# 04_-_MIPI_INTERFACE.net
KiCad netlist of a schematic drawn in Altium Designer
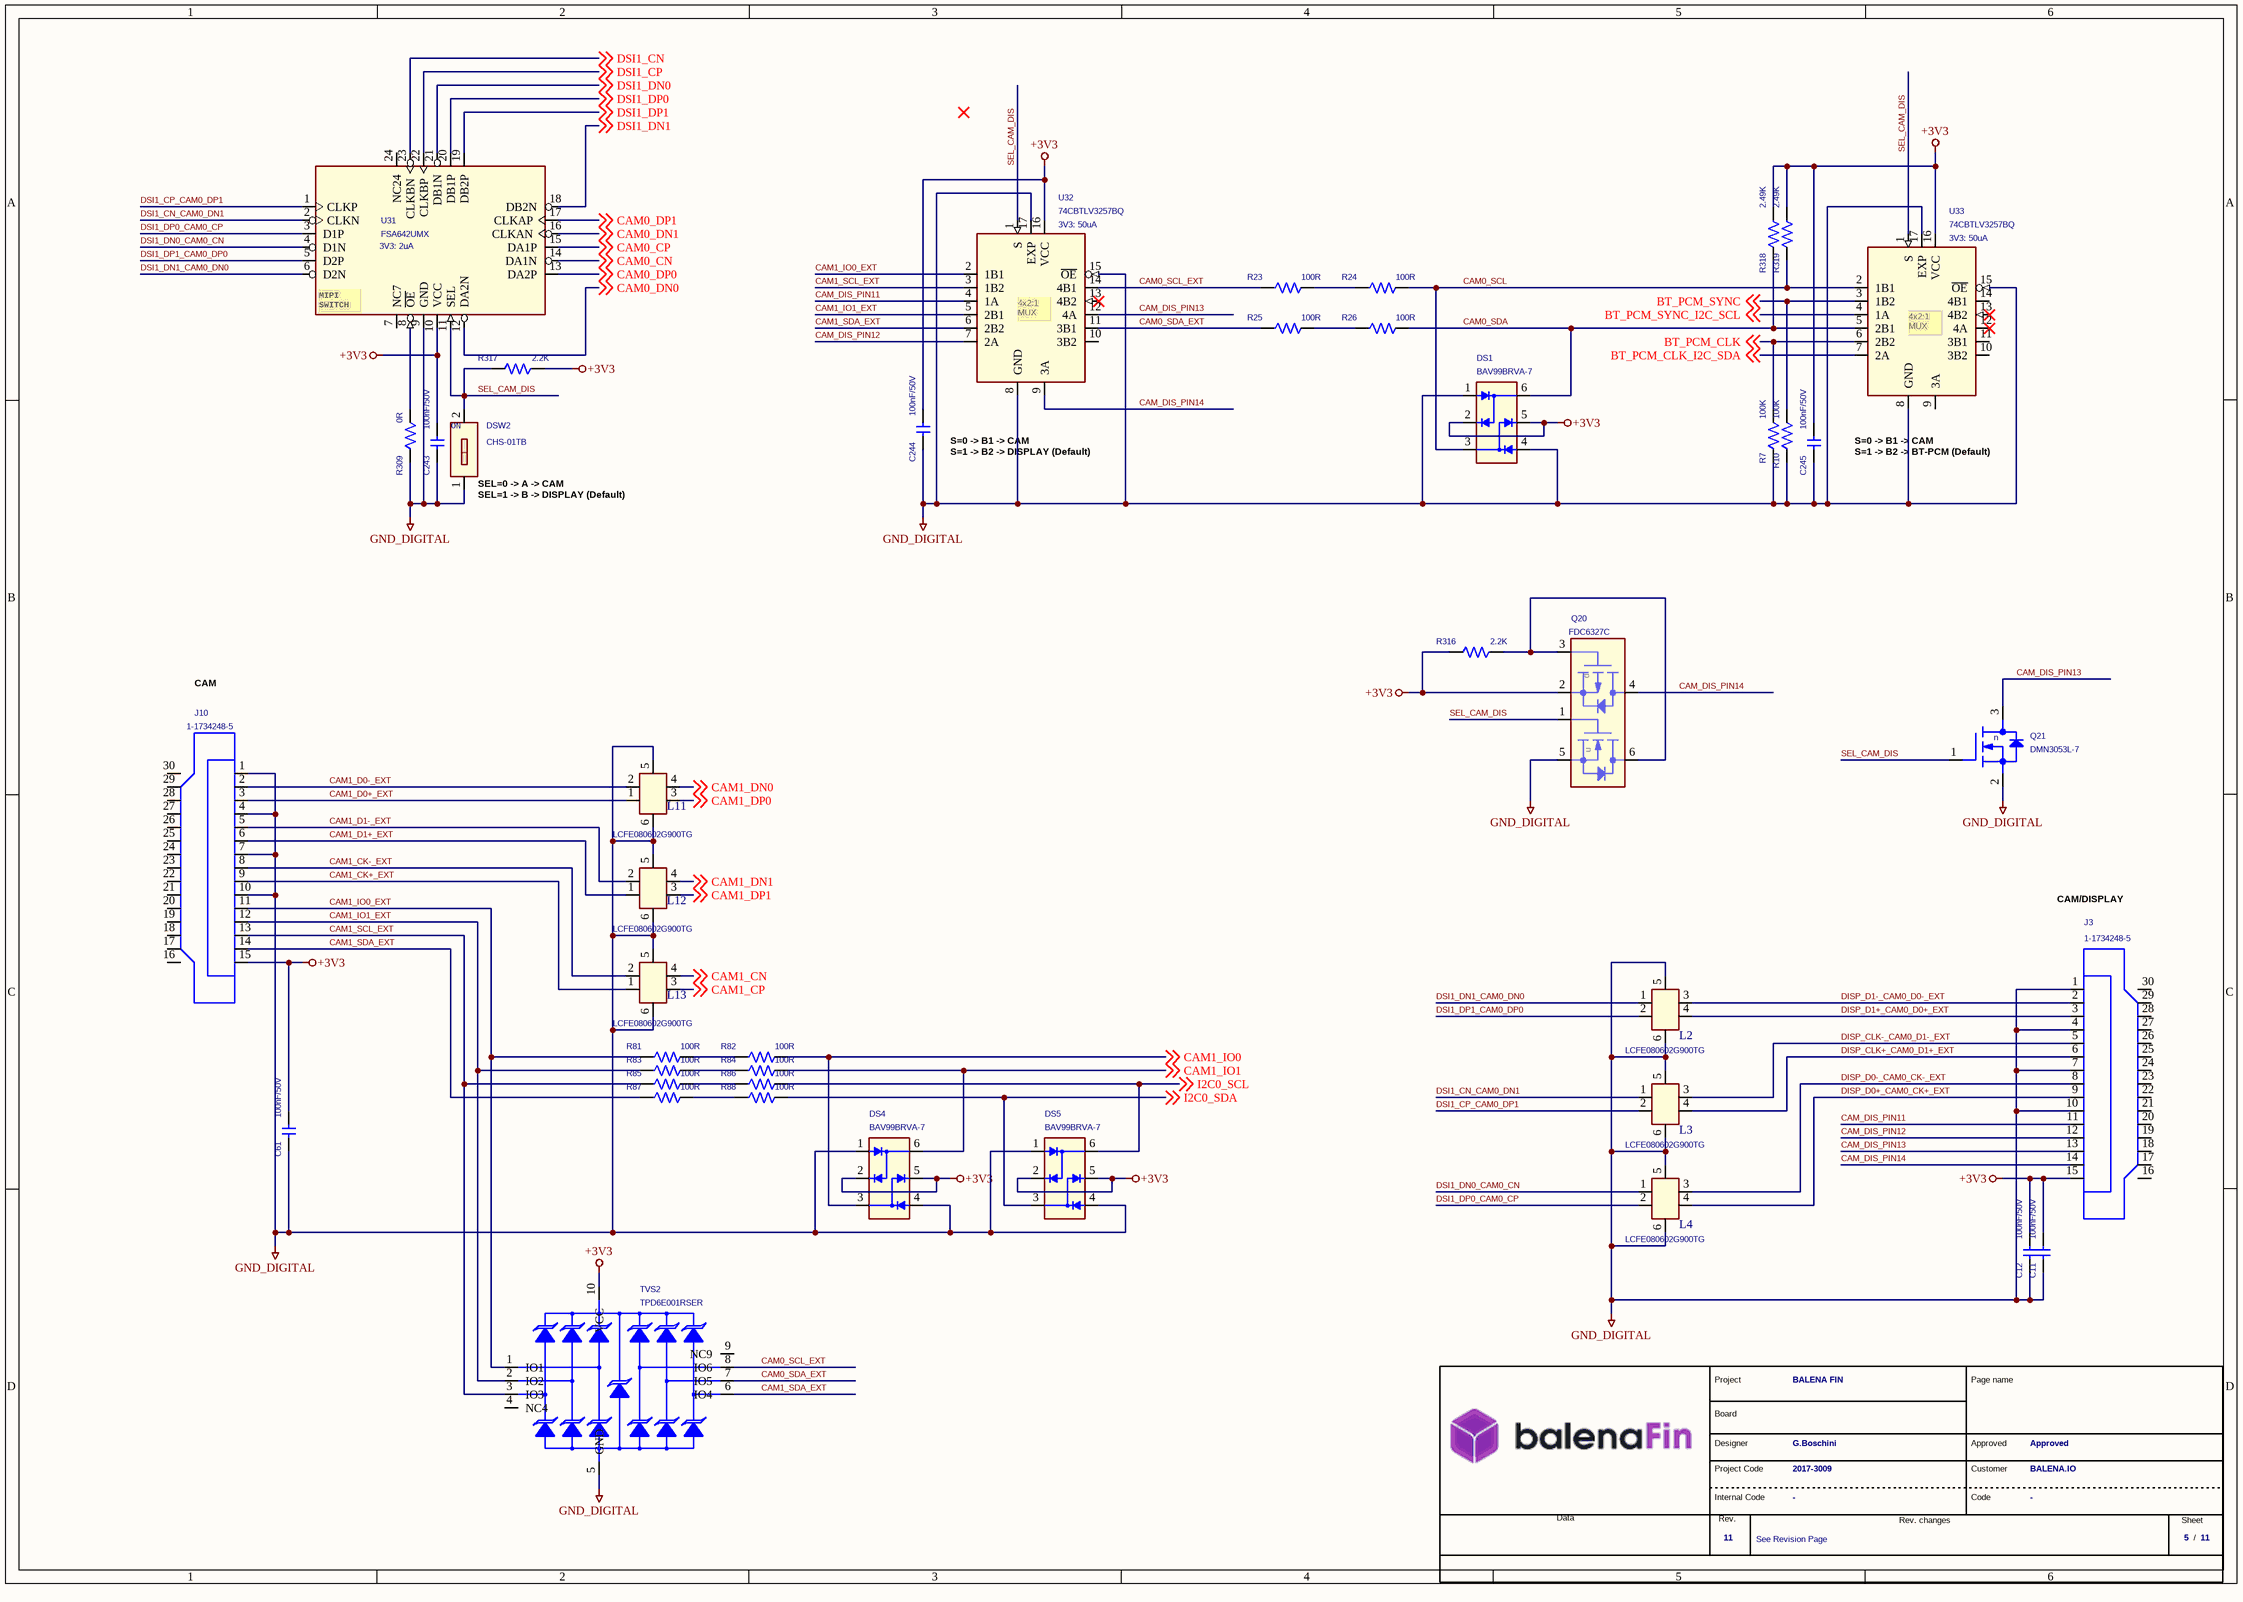
[diagram p0: 04 - MIPI INTERFACE.SchDoc]

(export (version "E")
  (design (tool "Eeschema 10.0.6"))
  (components
    (comp (ref "C11")
      (value "100nF/50V")
      (footprint "CS-C-0402")
      (description "CHIP CAP.CER. 100nF 16V 10% X7R 0402")
      (fields (field (name "MPN") "Generic"))
      (libsource (lib "*") (part "CS-C-0402-100n/16V"))
    )
    (comp (ref "C12")
      (value "100nF/50V")
      (footprint "CS-C-0402")
      (description "CHIP CAP.CER. 100nF 16V 10% X7R 0402")
      (fields (field (name "MPN") "Generic"))
      (libsource (lib "*") (part "CS-C-0402-100n/16V"))
    )
    (comp (ref "C61")
      (value "100nF/50V")
      (footprint "CS-C-0402")
      (description "CHIP CAP.CER. 100nF 16V 10% X7R 0402")
      (fields (field (name "MPN") "Generic"))
      (libsource (lib "*") (part "CS-C-0402-100n/16V"))
    )
    (comp (ref "C243")
      (value "100nF/50V")
      (footprint "CS-C-0402")
      (description "CHIP CAP.CER. 100nF 16V 10% X7R 0402")
      (fields (field (name "MPN") "Generic"))
      (libsource (lib "*") (part "CS-C-0402-100n/16V"))
    )
    (comp (ref "C244")
      (value "100nF/50V")
      (footprint "CS-C-0402")
      (description "CHIP CAP.CER. 100nF 16V 10% X7R 0402")
      (fields (field (name "MPN") "Generic"))
      (libsource (lib "*") (part "CS-C-0402-100n/16V"))
    )
    (comp (ref "C245")
      (value "100nF/50V")
      (footprint "CS-C-0402")
      (description "CHIP CAP.CER. 100nF 16V 10% X7R 0402")
      (fields (field (name "MPN") "Generic"))
      (libsource (lib "*") (part "CS-C-0402-100n/16V"))
    )
    (comp (ref "DS1")
      (value "BAV99BRVA-7")
      (footprint "SOT563")
      (description "Diode Switching 75V 0.215A 6-Pin SOT-563 T/R")
      (libsource (lib "*") (part "DIODO4x - BAV99BRVA-7 -0.2A/75V"))
    )
    (comp (ref "DS4")
      (value "BAV99BRVA-7")
      (footprint "SOT563")
      (description "Diode Switching 75V 0.215A 6-Pin SOT-563 T/R")
      (libsource (lib "*") (part "DIODO4x - BAV99BRVA-7 -0.2A/75V"))
    )
    (comp (ref "DS5")
      (value "BAV99BRVA-7")
      (footprint "SOT563")
      (description "Diode Switching 75V 0.215A 6-Pin SOT-563 T/R")
      (libsource (lib "*") (part "DIODO4x - BAV99BRVA-7 -0.2A/75V"))
    )
    (comp (ref "DSW2")
      (value "CHS-01TB")
      (footprint "DSS-CHS-01TB")
      (description "Dip Switch SPST 1 Position - Surface Mount Slide (Standard) - Actuator 100mA 6VDC")
      (libsource (lib "*") (part "DIP-SW-1x-CHS-01TB-SMD"))
    )
    (comp (ref "J3")
      (value "1-1734248-5")
      (footprint "J-15X2-0100-FDS-ZIF")
      (description "CONN FPC VERT 15POS 1.00MM SMD")
      (libsource (lib "*") (part "FPC-ZIF - J-15X2-0100-FDS-ZIF"))
    )
    (comp (ref "J10")
      (value "1-1734248-5")
      (footprint "J-15X2-0100-FDS-ZIF")
      (description "CONN FPC VERT 15POS 1.00MM SMD")
      (libsource (lib "*") (part "FPC-ZIF - J-15X2-0100-FDS-ZIF"))
    )
    (comp (ref "L2")
      (value "LCFE080602G900TG")
      (footprint "LCFE080602G900TG")
      (description "Common Mode Chokes / Filters 90ohms 25% 100A 2 Lines 0806")
      (libsource (lib "") (part "LCFE080602G900TG_1"))
    )
    (comp (ref "L3")
      (value "LCFE080602G900TG")
      (footprint "LCFE080602G900TG")
      (description "Common Mode Chokes / Filters 90ohms 25% 100A 2 Lines 0806")
      (libsource (lib "") (part "LCFE080602G900TG_1"))
    )
    (comp (ref "L4")
      (value "LCFE080602G900TG")
      (footprint "LCFE080602G900TG")
      (description "Common Mode Chokes / Filters 90ohms 25% 100A 2 Lines 0806")
      (libsource (lib "") (part "LCFE080602G900TG_1"))
    )
    (comp (ref "L11")
      (value "LCFE080602G900TG")
      (footprint "LCFE080602G900TG")
      (description "Common Mode Chokes / Filters 90ohms 25% 100A 2 Lines 0806")
      (libsource (lib "balenaFin_v1_x_x_Library") (part "LCFE080602G900TG"))
    )
    (comp (ref "L12")
      (value "LCFE080602G900TG")
      (footprint "LCFE080602G900TG")
      (description "Common Mode Chokes / Filters 90ohms 25% 100A 2 Lines 0806")
      (libsource (lib "balenaFin_v1_x_x_Library") (part "LCFE080602G900TG"))
    )
    (comp (ref "L13")
      (value "LCFE080602G900TG")
      (footprint "LCFE080602G900TG")
      (description "Common Mode Chokes / Filters 90ohms 25% 100A 2 Lines 0806")
      (libsource (lib "balenaFin_v1_x_x_Library") (part "LCFE080602G900TG"))
    )
    (comp (ref "Q20")
      (value "FDC6327C")
      (footprint "SOT23-6-DBV")
      (description "MOSFET N/P-CH 20V SSOT-6")
      (libsource (lib "*") (part "N-P MOS-FDC6327C-2.7A/1.9A/20V"))
    )
    (comp (ref "Q21")
      (value "DMN3053L-7")
      (footprint "SOT23")
      (description "MOSFET N-CH 30V 4A SOT23")
      (libsource (lib "*") (part "NMOS - DMN3053L-7 - 4A/30V"))
    )
    (comp (ref "R7")
      (value "100K")
      (footprint "RS-0402")
      (description "CHIP RES. 100K 0402 1/16W 1%")
      (fields (field (name "MPN") "Generic"))
      (libsource (lib "*") (part "RS-0402-100k"))
    )
    (comp (ref "R10")
      (value "100K")
      (footprint "RS-0402")
      (description "CHIP RES. 100K 0402 1/16W 1%")
      (fields (field (name "MPN") "Generic"))
      (libsource (lib "*") (part "RS-0402-100k"))
    )
    (comp (ref "R23")
      (value "100R")
      (footprint "RS-0402")
      (description "CHIP RES. 100R 0402 1/16W 1%")
      (fields (field (name "MPN") "Generic"))
      (libsource (lib "*") (part "RS-0402-100r"))
    )
    (comp (ref "R24")
      (value "100R")
      (footprint "RS-0402")
      (description "CHIP RES. 100R 0402 1/16W 1%")
      (fields (field (name "MPN") "Generic"))
      (libsource (lib "*") (part "RS-0402-100r"))
    )
    (comp (ref "R25")
      (value "100R")
      (footprint "RS-0402")
      (description "CHIP RES. 100R 0402 1/16W 1%")
      (fields (field (name "MPN") "Generic"))
      (libsource (lib "*") (part "RS-0402-100r"))
    )
    (comp (ref "R26")
      (value "100R")
      (footprint "RS-0402")
      (description "CHIP RES. 100R 0402 1/16W 1%")
      (fields (field (name "MPN") "Generic"))
      (libsource (lib "*") (part "RS-0402-100r"))
    )
    (comp (ref "R81")
      (value "100R")
      (footprint "RS-0402")
      (description "CHIP RES. 100R 0402 1/16W 1%")
      (fields (field (name "MPN") "Generic"))
      (libsource (lib "*") (part "RS-0402-100r"))
    )
    (comp (ref "R82")
      (value "100R")
      (footprint "RS-0402")
      (description "CHIP RES. 100R 0402 1/16W 1%")
      (fields (field (name "MPN") "Generic"))
      (libsource (lib "*") (part "RS-0402-100r"))
    )
    (comp (ref "R83")
      (value "100R")
      (footprint "RS-0402")
      (description "CHIP RES. 100R 0402 1/16W 1%")
      (fields (field (name "MPN") "Generic"))
      (libsource (lib "*") (part "RS-0402-100r"))
    )
    (comp (ref "R84")
      (value "100R")
      (footprint "RS-0402")
      (description "CHIP RES. 100R 0402 1/16W 1%")
      (fields (field (name "MPN") "Generic"))
      (libsource (lib "*") (part "RS-0402-100r"))
    )
    (comp (ref "R85")
      (value "100R")
      (footprint "RS-0402")
      (description "CHIP RES. 100R 0402 1/16W 1%")
      (fields (field (name "MPN") "Generic"))
      (libsource (lib "*") (part "RS-0402-100r"))
    )
    (comp (ref "R86")
      (value "100R")
      (footprint "RS-0402")
      (description "CHIP RES. 100R 0402 1/16W 1%")
      (fields (field (name "MPN") "Generic"))
      (libsource (lib "*") (part "RS-0402-100r"))
    )
    (comp (ref "R87")
      (value "100R")
      (footprint "RS-0402")
      (description "CHIP RES. 100R 0402 1/16W 1%")
      (fields (field (name "MPN") "Generic"))
      (libsource (lib "*") (part "RS-0402-100r"))
    )
    (comp (ref "R88")
      (value "100R")
      (footprint "RS-0402")
      (description "CHIP RES. 100R 0402 1/16W 1%")
      (fields (field (name "MPN") "Generic"))
      (libsource (lib "*") (part "RS-0402-100r"))
    )
    (comp (ref "R309")
      (value "0R")
      (footprint "RS-0402")
      (description "CHIP RES. 0R 0402 1/16W 1%")
      (fields (field (name "MPN") "Generic"))
      (libsource (lib "*") (part "RS-0402-0r"))
    )
    (comp (ref "R316")
      (value "2.2K")
      (footprint "RS-0402")
      (description "CHIP RES. 2K2 0402 1/16W 1%")
      (fields (field (name "MPN") "Generic"))
      (libsource (lib "*") (part "RS-0402-2.2k"))
    )
    (comp (ref "R317")
      (value "2.2K")
      (footprint "RS-0402")
      (description "CHIP RES. 2K2 0402 1/16W 1%")
      (fields (field (name "MPN") "Generic"))
      (libsource (lib "*") (part "RS-0402-2.2k"))
    )
    (comp (ref "R318")
      (value "2.49K")
      (footprint "RS-0402")
      (description "CHIP RES. 2K49 0402 1/16W 1% 100PPM/°C")
      (fields (field (name "MPN") "Generic"))
      (libsource (lib "*") (part "RS-0402-2.49k"))
    )
    (comp (ref "R319")
      (value "2.49K")
      (footprint "RS-0402")
      (description "CHIP RES. 2K49 0402 1/16W 1% 100PPM/°C")
      (fields (field (name "MPN") "Generic"))
      (libsource (lib "*") (part "RS-0402-2.49k"))
    )
    (comp (ref "TVS2")
      (value "TPD6E001RSER")
      (footprint "UFQFN10")
      (description "TVS DIODE 5VWM")
      (libsource (lib "*") (part "TVS-UNI6x - TPD6E001RSER"))
    )
    (comp (ref "U31")
      (value "FSA642UMX")
      (footprint "UFQFN24-0250X0340")
      (description "IC SWITCH 3PDT 24UMLP")
      (fields (field (name "POWER REQUIREMENTS") "3V3: 2uA"))
      (libsource (lib "*") (part "MIPI-SWITCH - FSA642UMX"))
    )
    (comp (ref "U32")
      (value "74CBTLV3257BQ")
      (footprint "VFQFN16-EXP-0250X0300")
      (description "IC MUX/DEMUX 4 X 1:2 16DHVQFN")
      (fields (field (name "POWER REQUIREMENTS") "3V3: 50uA"))
      (libsource (lib "*") (part "MUX-AN-4x2-1 - 74CBTLV3257BQ"))
    )
    (comp (ref "U33")
      (value "74CBTLV3257BQ")
      (footprint "VFQFN16-EXP-0250X0300")
      (description "IC MUX/DEMUX 4 X 1:2 16DHVQFN")
      (fields (field (name "POWER REQUIREMENTS") "3V3: 50uA"))
      (libsource (lib "*") (part "MUX-AN-4x2-1 - 74CBTLV3257BQ"))
    )
  )
  (nets
    (net (code "1") (name "+3V3") (class "Default")
      (node (ref "C11") (pin "1") (pinfunction "1_1") (pintype "passive"))
      (node (ref "C12") (pin "1") (pinfunction "1_1") (pintype "passive"))
      (node (ref "C243") (pin "1") (pinfunction "1_1") (pintype "passive"))
      (node (ref "C244") (pin "1") (pinfunction "1_1") (pintype "passive"))
      (node (ref "C245") (pin "1") (pinfunction "1_1") (pintype "passive"))
      (node (ref "C61") (pin "1") (pinfunction "1_1") (pintype "passive"))
      (node (ref "DS1") (pin "2") (pinfunction "C1_2") (pintype "passive"))
      (node (ref "DS1") (pin "5") (pinfunction "C2_5") (pintype "passive"))
      (node (ref "DS4") (pin "2") (pinfunction "C1_2") (pintype "passive"))
      (node (ref "DS4") (pin "5") (pinfunction "C2_5") (pintype "passive"))
      (node (ref "DS5") (pin "2") (pinfunction "C1_2") (pintype "passive"))
      (node (ref "DS5") (pin "5") (pinfunction "C2_5") (pintype "passive"))
      (node (ref "J10") (pin "15") (pinfunction "15_15") (pintype "passive"))
      (node (ref "J3") (pin "15") (pinfunction "15_15") (pintype "passive"))
      (node (ref "Q20") (pin "2") (pinfunction "S1_2") (pintype "passive"))
      (node (ref "R316") (pin "2") (pinfunction "2_2") (pintype "passive"))
      (node (ref "R317") (pin "1") (pinfunction "1_1") (pintype "passive"))
      (node (ref "R318") (pin "1") (pinfunction "1_1") (pintype "passive"))
      (node (ref "R319") (pin "1") (pinfunction "1_1") (pintype "passive"))
      (node (ref "TVS2") (pin "10") (pinfunction "VCC_10") (pintype "passive"))
      (node (ref "U31") (pin "10") (pinfunction "VCC_10") (pintype "power_in"))
      (node (ref "U32") (pin "16") (pinfunction "VCC_16") (pintype "power_in"))
      (node (ref "U33") (pin "16") (pinfunction "VCC_16") (pintype "power_in"))
    )
    (net (code "2") (name "/CAM0_SCL") (class "Default")
      (node (ref "DS1") (pin "3") (pinfunction "AC2_3") (pintype "passive"))
      (node (ref "R24") (pin "2") (pinfunction "2_2") (pintype "passive"))
      (node (ref "R319") (pin "2") (pinfunction "2_2") (pintype "passive"))
      (node (ref "U33") (pin "2") (pinfunction "1B1_2") (pintype "bidirectional"))
    )
    (net (code "3") (name "/CAM0_SCL_EXT") (class "Default")
      (node (ref "R23") (pin "1") (pinfunction "1_1") (pintype "passive"))
      (node (ref "TVS2") (pin "8") (pinfunction "IO6_8") (pintype "passive"))
      (node (ref "U32") (pin "14") (pinfunction "4B1_14") (pintype "bidirectional"))
    )
    (net (code "4") (name "/CAM0_SDA") (class "Default")
      (node (ref "DS1") (pin "6") (pinfunction "AC1_6") (pintype "passive"))
      (node (ref "R26") (pin "2") (pinfunction "2_2") (pintype "passive"))
      (node (ref "R318") (pin "2") (pinfunction "2_2") (pintype "passive"))
      (node (ref "U33") (pin "5") (pinfunction "2B1_5") (pintype "bidirectional"))
    )
    (net (code "5") (name "/CAM0_SDA_EXT") (class "Default")
      (node (ref "R25") (pin "1") (pinfunction "1_1") (pintype "passive"))
      (node (ref "TVS2") (pin "7") (pinfunction "IO5_7") (pintype "passive"))
      (node (ref "U32") (pin "11") (pinfunction "3B1_11") (pintype "bidirectional"))
    )
    (net (code "6") (name "/CAM1_CK+_EXT") (class "Default")
      (node (ref "J10") (pin "9") (pinfunction "9_9") (pintype "passive"))
      (node (ref "L13") (pin "1") (pinfunction "1_1") (pintype "passive"))
    )
    (net (code "7") (name "/CAM1_CK-_EXT") (class "Default")
      (node (ref "J10") (pin "8") (pinfunction "8_8") (pintype "passive"))
      (node (ref "L13") (pin "2") (pinfunction "2_2") (pintype "passive"))
    )
    (net (code "8") (name "/CAM1_D0+_EXT") (class "Default")
      (node (ref "J10") (pin "3") (pinfunction "3_3") (pintype "passive"))
      (node (ref "L11") (pin "1") (pinfunction "1_1") (pintype "passive"))
    )
    (net (code "9") (name "/CAM1_D0-_EXT") (class "Default")
      (node (ref "J10") (pin "2") (pinfunction "2_2") (pintype "passive"))
      (node (ref "L11") (pin "2") (pinfunction "2_2") (pintype "passive"))
    )
    (net (code "10") (name "/CAM1_D1+_EXT") (class "Default")
      (node (ref "J10") (pin "6") (pinfunction "6_6") (pintype "passive"))
      (node (ref "L12") (pin "1") (pinfunction "1_1") (pintype "passive"))
    )
    (net (code "11") (name "/CAM1_D1-_EXT") (class "Default")
      (node (ref "J10") (pin "5") (pinfunction "5_5") (pintype "passive"))
      (node (ref "L12") (pin "2") (pinfunction "2_2") (pintype "passive"))
    )
    (net (code "12") (name "/CAM1_IO0_EXT") (class "Default")
      (node (ref "J10") (pin "11") (pinfunction "11_11") (pintype "passive"))
      (node (ref "R81") (pin "1") (pinfunction "1_1") (pintype "passive"))
      (node (ref "TVS2") (pin "1") (pinfunction "IO1_1") (pintype "passive"))
      (node (ref "U32") (pin "2") (pinfunction "1B1_2") (pintype "bidirectional"))
    )
    (net (code "13") (name "/CAM1_IO1_EXT") (class "Default")
      (node (ref "J10") (pin "12") (pinfunction "12_12") (pintype "passive"))
      (node (ref "R83") (pin "1") (pinfunction "1_1") (pintype "passive"))
      (node (ref "TVS2") (pin "2") (pinfunction "IO2_2") (pintype "passive"))
      (node (ref "U32") (pin "5") (pinfunction "2B1_5") (pintype "bidirectional"))
    )
    (net (code "14") (name "/CAM1_SCL_EXT") (class "Default")
      (node (ref "J10") (pin "13") (pinfunction "13_13") (pintype "passive"))
      (node (ref "R85") (pin "1") (pinfunction "1_1") (pintype "passive"))
      (node (ref "TVS2") (pin "3") (pinfunction "IO3_3") (pintype "passive"))
      (node (ref "U32") (pin "3") (pinfunction "1B2_3") (pintype "bidirectional"))
    )
    (net (code "15") (name "/CAM1_SDA_EXT") (class "Default")
      (node (ref "J10") (pin "14") (pinfunction "14_14") (pintype "passive"))
      (node (ref "R87") (pin "1") (pinfunction "1_1") (pintype "passive"))
      (node (ref "TVS2") (pin "6") (pinfunction "IO4_6") (pintype "passive"))
      (node (ref "U32") (pin "6") (pinfunction "2B2_6") (pintype "bidirectional"))
    )
    (net (code "16") (name "/CAM_DIS_PIN11") (class "Default")
      (node (ref "J3") (pin "11") (pinfunction "11_11") (pintype "passive"))
      (node (ref "U32") (pin "4") (pinfunction "1A_4") (pintype "bidirectional"))
    )
    (net (code "17") (name "/CAM_DIS_PIN12") (class "Default")
      (node (ref "J3") (pin "12") (pinfunction "12_12") (pintype "passive"))
      (node (ref "U32") (pin "7") (pinfunction "2A_7") (pintype "bidirectional"))
    )
    (net (code "18") (name "/CAM_DIS_PIN13") (class "Default")
      (node (ref "J3") (pin "13") (pinfunction "13_13") (pintype "passive"))
      (node (ref "Q21") (pin "3") (pinfunction "D_3") (pintype "passive"))
      (node (ref "U32") (pin "12") (pinfunction "4A_12") (pintype "bidirectional"))
    )
    (net (code "19") (name "/CAM_DIS_PIN14") (class "Default")
      (node (ref "J3") (pin "14") (pinfunction "14_14") (pintype "passive"))
      (node (ref "Q20") (pin "4") (pinfunction "D1_4") (pintype "passive"))
      (node (ref "U32") (pin "9") (pinfunction "3A_9") (pintype "bidirectional"))
    )
    (net (code "20") (name "/DISP_CLK+_CAM0_D1+_EXT") (class "Default")
      (node (ref "J3") (pin "6") (pinfunction "6_6") (pintype "passive"))
      (node (ref "L3") (pin "4") (pinfunction "4_4") (pintype "passive"))
    )
    (net (code "21") (name "/DISP_CLK-_CAM0_D1-_EXT") (class "Default")
      (node (ref "J3") (pin "5") (pinfunction "5_5") (pintype "passive"))
      (node (ref "L3") (pin "3") (pinfunction "3_3") (pintype "passive"))
    )
    (net (code "22") (name "/DISP_D0+_CAM0_CK+_EXT") (class "Default")
      (node (ref "J3") (pin "9") (pinfunction "9_9") (pintype "passive"))
      (node (ref "L4") (pin "4") (pinfunction "4_4") (pintype "passive"))
    )
    (net (code "23") (name "/DISP_D0-_CAM0_CK-_EXT") (class "Default")
      (node (ref "J3") (pin "8") (pinfunction "8_8") (pintype "passive"))
      (node (ref "L4") (pin "3") (pinfunction "3_3") (pintype "passive"))
    )
    (net (code "24") (name "/DISP_D1+_CAM0_D0+_EXT") (class "Default")
      (node (ref "J3") (pin "3") (pinfunction "3_3") (pintype "passive"))
      (node (ref "L2") (pin "4") (pinfunction "4_4") (pintype "passive"))
    )
    (net (code "25") (name "/DISP_D1-_CAM0_D0-_EXT") (class "Default")
      (node (ref "J3") (pin "2") (pinfunction "2_2") (pintype "passive"))
      (node (ref "L2") (pin "3") (pinfunction "3_3") (pintype "passive"))
    )
    (net (code "26") (name "/DSI1_CN_CAM0_DN1") (class "Default")
      (node (ref "L3") (pin "1") (pinfunction "1_1") (pintype "passive"))
      (node (ref "U31") (pin "2") (pinfunction "CLKN_2") (pintype "bidirectional"))
    )
    (net (code "27") (name "/DSI1_CP_CAM0_DP1") (class "Default")
      (node (ref "L3") (pin "2") (pinfunction "2_2") (pintype "passive"))
      (node (ref "U31") (pin "1") (pinfunction "CLKP_1") (pintype "bidirectional"))
    )
    (net (code "28") (name "/DSI1_DN0_CAM0_CN") (class "Default")
      (node (ref "L4") (pin "1") (pinfunction "1_1") (pintype "passive"))
      (node (ref "U31") (pin "4") (pinfunction "D1N_4") (pintype "bidirectional"))
    )
    (net (code "29") (name "/DSI1_DN1_CAM0_DN0") (class "Default")
      (node (ref "L2") (pin "1") (pinfunction "1_1") (pintype "passive"))
      (node (ref "U31") (pin "6") (pinfunction "D2N_6") (pintype "bidirectional"))
    )
    (net (code "30") (name "/DSI1_DP0_CAM0_CP") (class "Default")
      (node (ref "L4") (pin "2") (pinfunction "2_2") (pintype "passive"))
      (node (ref "U31") (pin "3") (pinfunction "D1P_3") (pintype "bidirectional"))
    )
    (net (code "31") (name "/DSI1_DP1_CAM0_DP0") (class "Default")
      (node (ref "L2") (pin "2") (pinfunction "2_2") (pintype "passive"))
      (node (ref "U31") (pin "5") (pinfunction "D2P_5") (pintype "bidirectional"))
    )
    (net (code "32") (name "/SEL_CAM_DIS") (class "Default")
      (node (ref "DSW2") (pin "2") (pinfunction "2_2") (pintype "passive"))
      (node (ref "Q20") (pin "1") (pinfunction "G2_1") (pintype "passive"))
      (node (ref "Q21") (pin "1") (pinfunction "G_1") (pintype "passive"))
      (node (ref "R317") (pin "2") (pinfunction "2_2") (pintype "passive"))
      (node (ref "U31") (pin "11") (pinfunction "SEL_11") (pintype "input"))
      (node (ref "U32") (pin "1") (pinfunction "S_1") (pintype "input"))
      (node (ref "U33") (pin "1") (pinfunction "S_1") (pintype "input"))
    )
    (net (code "33") (name "BT_PCM_CLK") (class "Default")
      (node (ref "R7") (pin "2") (pinfunction "2_2") (pintype "passive"))
      (node (ref "U33") (pin "6") (pinfunction "2B2_6") (pintype "bidirectional"))
    )
    (net (code "34") (name "BT_PCM_CLK_I2C_SDA") (class "Default")
      (node (ref "U33") (pin "7") (pinfunction "2A_7") (pintype "bidirectional"))
    )
    (net (code "35") (name "BT_PCM_SYNC") (class "Default")
      (node (ref "R10") (pin "2") (pinfunction "2_2") (pintype "passive"))
      (node (ref "U33") (pin "3") (pinfunction "1B2_3") (pintype "bidirectional"))
    )
    (net (code "36") (name "BT_PCM_SYNC_I2C_SCL") (class "Default")
      (node (ref "U33") (pin "4") (pinfunction "1A_4") (pintype "bidirectional"))
    )
    (net (code "37") (name "CAM0_CN") (class "Default")
      (node (ref "U31") (pin "14") (pinfunction "DA1N_14") (pintype "bidirectional"))
    )
    (net (code "38") (name "CAM0_CP") (class "Default")
      (node (ref "U31") (pin "15") (pinfunction "DA1P_15") (pintype "bidirectional"))
    )
    (net (code "39") (name "CAM0_DN0") (class "Default")
      (node (ref "U31") (pin "12") (pinfunction "DA2N_12") (pintype "bidirectional"))
    )
    (net (code "40") (name "CAM0_DN1") (class "Default")
      (node (ref "U31") (pin "16") (pinfunction "CLKAN_16") (pintype "bidirectional"))
    )
    (net (code "41") (name "CAM0_DP0") (class "Default")
      (node (ref "U31") (pin "13") (pinfunction "DA2P_13") (pintype "bidirectional"))
    )
    (net (code "42") (name "CAM0_DP1") (class "Default")
      (node (ref "U31") (pin "17") (pinfunction "CLKAP_17") (pintype "bidirectional"))
    )
    (net (code "43") (name "CAM1_CN") (class "Default")
      (node (ref "L13") (pin "4") (pinfunction "4_4") (pintype "passive"))
    )
    (net (code "44") (name "CAM1_CP") (class "Default")
      (node (ref "L13") (pin "3") (pinfunction "3_3") (pintype "passive"))
    )
    (net (code "45") (name "CAM1_DN0") (class "Default")
      (node (ref "L11") (pin "4") (pinfunction "4_4") (pintype "passive"))
    )
    (net (code "46") (name "CAM1_DN1") (class "Default")
      (node (ref "L12") (pin "4") (pinfunction "4_4") (pintype "passive"))
    )
    (net (code "47") (name "CAM1_DP0") (class "Default")
      (node (ref "L11") (pin "3") (pinfunction "3_3") (pintype "passive"))
    )
    (net (code "48") (name "CAM1_DP1") (class "Default")
      (node (ref "L12") (pin "3") (pinfunction "3_3") (pintype "passive"))
    )
    (net (code "49") (name "CAM1_IO0") (class "Default")
      (node (ref "DS4") (pin "3") (pinfunction "AC2_3") (pintype "passive"))
      (node (ref "R82") (pin "2") (pinfunction "2_2") (pintype "passive"))
    )
    (net (code "50") (name "CAM1_IO1") (class "Default")
      (node (ref "DS4") (pin "6") (pinfunction "AC1_6") (pintype "passive"))
      (node (ref "R84") (pin "2") (pinfunction "2_2") (pintype "passive"))
    )
    (net (code "51") (name "DSI1_CN") (class "Default")
      (node (ref "U31") (pin "23") (pinfunction "CLKBN_23") (pintype "bidirectional"))
    )
    (net (code "52") (name "DSI1_CP") (class "Default")
      (node (ref "U31") (pin "22") (pinfunction "CLKBP_22") (pintype "bidirectional"))
    )
    (net (code "53") (name "DSI1_DN0") (class "Default")
      (node (ref "U31") (pin "21") (pinfunction "DB1N_21") (pintype "bidirectional"))
    )
    (net (code "54") (name "DSI1_DN1") (class "Default")
      (node (ref "U31") (pin "18") (pinfunction "DB2N_18") (pintype "bidirectional"))
    )
    (net (code "55") (name "DSI1_DP0") (class "Default")
      (node (ref "U31") (pin "20") (pinfunction "DB1P_20") (pintype "bidirectional"))
    )
    (net (code "56") (name "DSI1_DP1") (class "Default")
      (node (ref "U31") (pin "19") (pinfunction "DB2P_19") (pintype "bidirectional"))
    )
    (net (code "57") (name "GND_DIGITAL") (class "Default")
      (node (ref "C11") (pin "2") (pinfunction "2_2") (pintype "passive"))
      (node (ref "C12") (pin "2") (pinfunction "2_2") (pintype "passive"))
      (node (ref "C243") (pin "2") (pinfunction "2_2") (pintype "passive"))
      (node (ref "C244") (pin "2") (pinfunction "2_2") (pintype "passive"))
      (node (ref "C245") (pin "2") (pinfunction "2_2") (pintype "passive"))
      (node (ref "C61") (pin "2") (pinfunction "2_2") (pintype "passive"))
      (node (ref "DS1") (pin "1") (pinfunction "A1_1") (pintype "passive"))
      (node (ref "DS1") (pin "4") (pinfunction "A2_4") (pintype "passive"))
      (node (ref "DS4") (pin "1") (pinfunction "A1_1") (pintype "passive"))
      (node (ref "DS4") (pin "4") (pinfunction "A2_4") (pintype "passive"))
      (node (ref "DS5") (pin "1") (pinfunction "A1_1") (pintype "passive"))
      (node (ref "DS5") (pin "4") (pinfunction "A2_4") (pintype "passive"))
      (node (ref "DSW2") (pin "1") (pinfunction "1_1") (pintype "passive"))
      (node (ref "J10") (pin "1") (pinfunction "1_1") (pintype "passive"))
      (node (ref "J10") (pin "10") (pinfunction "10_10") (pintype "passive"))
      (node (ref "J10") (pin "4") (pinfunction "4_4") (pintype "passive"))
      (node (ref "J10") (pin "7") (pinfunction "7_7") (pintype "passive"))
      (node (ref "J3") (pin "1") (pinfunction "1_1") (pintype "passive"))
      (node (ref "J3") (pin "10") (pinfunction "10_10") (pintype "passive"))
      (node (ref "J3") (pin "4") (pinfunction "4_4") (pintype "passive"))
      (node (ref "J3") (pin "7") (pinfunction "7_7") (pintype "passive"))
      (node (ref "L11") (pin "5") (pinfunction "5_5") (pintype "power_in"))
      (node (ref "L11") (pin "6") (pinfunction "6_6") (pintype "power_in"))
      (node (ref "L12") (pin "5") (pinfunction "5_5") (pintype "power_in"))
      (node (ref "L12") (pin "6") (pinfunction "6_6") (pintype "power_in"))
      (node (ref "L13") (pin "5") (pinfunction "5_5") (pintype "power_in"))
      (node (ref "L13") (pin "6") (pinfunction "6_6") (pintype "power_in"))
      (node (ref "L2") (pin "5") (pinfunction "5_5") (pintype "power_in"))
      (node (ref "L2") (pin "6") (pinfunction "6_6") (pintype "power_in"))
      (node (ref "L3") (pin "5") (pinfunction "5_5") (pintype "power_in"))
      (node (ref "L3") (pin "6") (pinfunction "6_6") (pintype "power_in"))
      (node (ref "L4") (pin "5") (pinfunction "5_5") (pintype "power_in"))
      (node (ref "L4") (pin "6") (pinfunction "6_6") (pintype "power_in"))
      (node (ref "Q20") (pin "5") (pinfunction "S2_5") (pintype "passive"))
      (node (ref "Q21") (pin "2") (pinfunction "S_2") (pintype "passive"))
      (node (ref "R10") (pin "1") (pinfunction "1_1") (pintype "passive"))
      (node (ref "R309") (pin "1") (pinfunction "1_1") (pintype "passive"))
      (node (ref "R7") (pin "1") (pinfunction "1_1") (pintype "passive"))
      (node (ref "TVS2") (pin "5") (pinfunction "GND_5") (pintype "power_in"))
      (node (ref "U31") (pin "9") (pinfunction "GND_9") (pintype "power_in"))
      (node (ref "U32") (pin "15") (pinfunction "~{OE}_15") (pintype "input"))
      (node (ref "U32") (pin "17") (pinfunction "EXP_17") (pintype "passive"))
      (node (ref "U32") (pin "8") (pinfunction "GND_8") (pintype "power_in"))
      (node (ref "U33") (pin "15") (pinfunction "~{OE}_15") (pintype "input"))
      (node (ref "U33") (pin "17") (pinfunction "EXP_17") (pintype "passive"))
      (node (ref "U33") (pin "8") (pinfunction "GND_8") (pintype "power_in"))
    )
    (net (code "58") (name "I2C0_SCL") (class "Default")
      (node (ref "DS5") (pin "6") (pinfunction "AC1_6") (pintype "passive"))
      (node (ref "R86") (pin "2") (pinfunction "2_2") (pintype "passive"))
    )
    (net (code "59") (name "I2C0_SDA") (class "Default")
      (node (ref "DS5") (pin "3") (pinfunction "AC2_3") (pintype "passive"))
      (node (ref "R88") (pin "2") (pinfunction "2_2") (pintype "passive"))
    )
    (net (code "60") (name "Net-(Q20-D2)") (class "Default")
      (node (ref "Q20") (pin "3") (pinfunction "G1_3") (pintype "passive"))
      (node (ref "Q20") (pin "6") (pinfunction "D2_6") (pintype "passive"))
      (node (ref "R316") (pin "1") (pinfunction "1_1") (pintype "passive"))
    )
    (net (code "61") (name "Net-(R23-Pad2)") (class "Default")
      (node (ref "R23") (pin "2") (pinfunction "2_2") (pintype "passive"))
      (node (ref "R24") (pin "1") (pinfunction "1_1") (pintype "passive"))
    )
    (net (code "62") (name "Net-(R25-Pad2)") (class "Default")
      (node (ref "R25") (pin "2") (pinfunction "2_2") (pintype "passive"))
      (node (ref "R26") (pin "1") (pinfunction "1_1") (pintype "passive"))
    )
    (net (code "63") (name "Net-(R81-Pad2)") (class "Default")
      (node (ref "R81") (pin "2") (pinfunction "2_2") (pintype "passive"))
      (node (ref "R82") (pin "1") (pinfunction "1_1") (pintype "passive"))
    )
    (net (code "64") (name "Net-(R83-Pad2)") (class "Default")
      (node (ref "R83") (pin "2") (pinfunction "2_2") (pintype "passive"))
      (node (ref "R84") (pin "1") (pinfunction "1_1") (pintype "passive"))
    )
    (net (code "65") (name "Net-(R85-Pad2)") (class "Default")
      (node (ref "R85") (pin "2") (pinfunction "2_2") (pintype "passive"))
      (node (ref "R86") (pin "1") (pinfunction "1_1") (pintype "passive"))
    )
    (net (code "66") (name "Net-(R87-Pad2)") (class "Default")
      (node (ref "R87") (pin "2") (pinfunction "2_2") (pintype "passive"))
      (node (ref "R88") (pin "1") (pinfunction "1_1") (pintype "passive"))
    )
    (net (code "67") (name "Net-(U31-~{OE})") (class "Default")
      (node (ref "R309") (pin "2") (pinfunction "2_2") (pintype "passive"))
      (node (ref "U31") (pin "8") (pinfunction "~{OE}_8") (pintype "input"))
    )
    (net (code "68") (name "unconnected-(J3-Pad16)") (class "Default")
      (node (ref "J3") (pin "16") (pinfunction "16_16") (pintype "passive"))
    )
    (net (code "69") (name "unconnected-(J3-Pad17)") (class "Default")
      (node (ref "J3") (pin "17") (pinfunction "17_17") (pintype "passive"))
    )
    (net (code "70") (name "unconnected-(J3-Pad18)") (class "Default")
      (node (ref "J3") (pin "18") (pinfunction "18_18") (pintype "passive"))
    )
    (net (code "71") (name "unconnected-(J3-Pad19)") (class "Default")
      (node (ref "J3") (pin "19") (pinfunction "19_19") (pintype "passive"))
    )
    (net (code "72") (name "unconnected-(J3-Pad20)") (class "Default")
      (node (ref "J3") (pin "20") (pinfunction "20_20") (pintype "passive"))
    )
    (net (code "73") (name "unconnected-(J3-Pad21)") (class "Default")
      (node (ref "J3") (pin "21") (pinfunction "21_21") (pintype "passive"))
    )
    (net (code "74") (name "unconnected-(J3-Pad22)") (class "Default")
      (node (ref "J3") (pin "22") (pinfunction "22_22") (pintype "passive"))
    )
    (net (code "75") (name "unconnected-(J3-Pad23)") (class "Default")
      (node (ref "J3") (pin "23") (pinfunction "23_23") (pintype "passive"))
    )
    (net (code "76") (name "unconnected-(J3-Pad24)") (class "Default")
      (node (ref "J3") (pin "24") (pinfunction "24_24") (pintype "passive"))
    )
    (net (code "77") (name "unconnected-(J3-Pad25)") (class "Default")
      (node (ref "J3") (pin "25") (pinfunction "25_25") (pintype "passive"))
    )
    (net (code "78") (name "unconnected-(J3-Pad26)") (class "Default")
      (node (ref "J3") (pin "26") (pinfunction "26_26") (pintype "passive"))
    )
    (net (code "79") (name "unconnected-(J3-Pad27)") (class "Default")
      (node (ref "J3") (pin "27") (pinfunction "27_27") (pintype "passive"))
    )
    (net (code "80") (name "unconnected-(J3-Pad28)") (class "Default")
      (node (ref "J3") (pin "28") (pinfunction "28_28") (pintype "passive"))
    )
    (net (code "81") (name "unconnected-(J3-Pad29)") (class "Default")
      (node (ref "J3") (pin "29") (pinfunction "29_29") (pintype "passive"))
    )
    (net (code "82") (name "unconnected-(J3-Pad30)") (class "Default")
      (node (ref "J3") (pin "30") (pinfunction "30_30") (pintype "passive"))
    )
    (net (code "83") (name "unconnected-(J10-Pad16)") (class "Default")
      (node (ref "J10") (pin "16") (pinfunction "16_16") (pintype "passive"))
    )
    (net (code "84") (name "unconnected-(J10-Pad17)") (class "Default")
      (node (ref "J10") (pin "17") (pinfunction "17_17") (pintype "passive"))
    )
    (net (code "85") (name "unconnected-(J10-Pad18)") (class "Default")
      (node (ref "J10") (pin "18") (pinfunction "18_18") (pintype "passive"))
    )
    (net (code "86") (name "unconnected-(J10-Pad19)") (class "Default")
      (node (ref "J10") (pin "19") (pinfunction "19_19") (pintype "passive"))
    )
    (net (code "87") (name "unconnected-(J10-Pad20)") (class "Default")
      (node (ref "J10") (pin "20") (pinfunction "20_20") (pintype "passive"))
    )
    (net (code "88") (name "unconnected-(J10-Pad21)") (class "Default")
      (node (ref "J10") (pin "21") (pinfunction "21_21") (pintype "passive"))
    )
    (net (code "89") (name "unconnected-(J10-Pad22)") (class "Default")
      (node (ref "J10") (pin "22") (pinfunction "22_22") (pintype "passive"))
    )
    (net (code "90") (name "unconnected-(J10-Pad23)") (class "Default")
      (node (ref "J10") (pin "23") (pinfunction "23_23") (pintype "passive"))
    )
    (net (code "91") (name "unconnected-(J10-Pad24)") (class "Default")
      (node (ref "J10") (pin "24") (pinfunction "24_24") (pintype "passive"))
    )
    (net (code "92") (name "unconnected-(J10-Pad25)") (class "Default")
      (node (ref "J10") (pin "25") (pinfunction "25_25") (pintype "passive"))
    )
    (net (code "93") (name "unconnected-(J10-Pad26)") (class "Default")
      (node (ref "J10") (pin "26") (pinfunction "26_26") (pintype "passive"))
    )
    (net (code "94") (name "unconnected-(J10-Pad27)") (class "Default")
      (node (ref "J10") (pin "27") (pinfunction "27_27") (pintype "passive"))
    )
    (net (code "95") (name "unconnected-(J10-Pad28)") (class "Default")
      (node (ref "J10") (pin "28") (pinfunction "28_28") (pintype "passive"))
    )
    (net (code "96") (name "unconnected-(J10-Pad29)") (class "Default")
      (node (ref "J10") (pin "29") (pinfunction "29_29") (pintype "passive"))
    )
    (net (code "97") (name "unconnected-(J10-Pad30)") (class "Default")
      (node (ref "J10") (pin "30") (pinfunction "30_30") (pintype "passive"))
    )
    (net (code "98") (name "unconnected-(TVS2-NC4-Pad4)") (class "Default")
      (node (ref "TVS2") (pin "4") (pinfunction "NC4_4") (pintype "passive"))
    )
    (net (code "99") (name "unconnected-(TVS2-NC9-Pad9)") (class "Default")
      (node (ref "TVS2") (pin "9") (pinfunction "NC9_9") (pintype "passive"))
    )
    (net (code "100") (name "unconnected-(U31-NC7-Pad7)") (class "Default")
      (node (ref "U31") (pin "7") (pinfunction "NC7_7") (pintype "passive"))
    )
    (net (code "101") (name "unconnected-(U31-NC24-Pad24)") (class "Default")
      (node (ref "U31") (pin "24") (pinfunction "NC24_24") (pintype "passive"))
    )
    (net (code "102") (name "unconnected-(U32-3B2-Pad10)") (class "Default")
      (node (ref "U32") (pin "10") (pinfunction "3B2_10") (pintype "bidirectional"))
    )
    (net (code "103") (name "unconnected-(U32-4B2-Pad13)") (class "Default")
      (node (ref "U32") (pin "13") (pinfunction "4B2_13") (pintype "input+no_connect"))
    )
    (net (code "104") (name "unconnected-(U33-3A-Pad9)") (class "Default")
      (node (ref "U33") (pin "9") (pinfunction "3A_9") (pintype "bidirectional"))
    )
    (net (code "105") (name "unconnected-(U33-3B1-Pad11)") (class "Default")
      (node (ref "U33") (pin "11") (pinfunction "3B1_11") (pintype "bidirectional"))
    )
    (net (code "106") (name "unconnected-(U33-3B2-Pad10)") (class "Default")
      (node (ref "U33") (pin "10") (pinfunction "3B2_10") (pintype "bidirectional"))
    )
    (net (code "107") (name "unconnected-(U33-4A-Pad12)") (class "Default")
      (node (ref "U33") (pin "12") (pinfunction "4A_12") (pintype "bidirectional+no_connect"))
    )
    (net (code "108") (name "unconnected-(U33-4B1-Pad14)") (class "Default")
      (node (ref "U33") (pin "14") (pinfunction "4B1_14") (pintype "bidirectional"))
    )
    (net (code "109") (name "unconnected-(U33-4B2-Pad13)") (class "Default")
      (node (ref "U33") (pin "13") (pinfunction "4B2_13") (pintype "input+no_connect"))
    )
  )
)
